# 03_MCU.net
KiCad netlist of a schematic drawn in Altium Designer
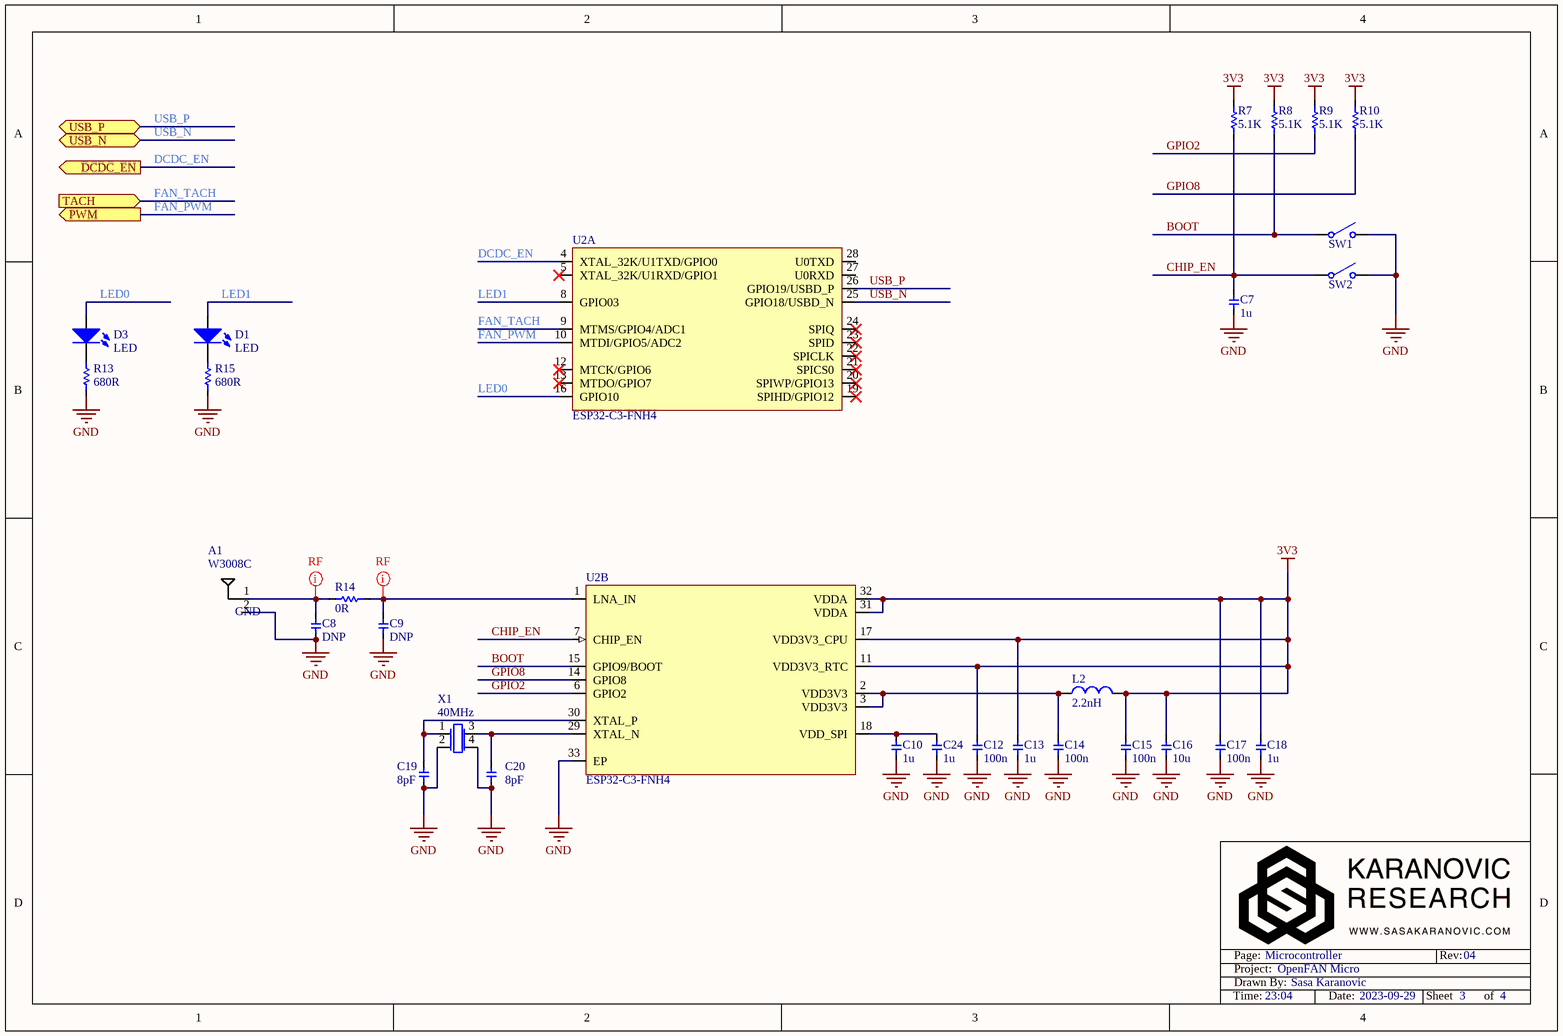
[diagram p0: 03_MCU.SchDoc]

(export (version "E")
  (design (tool "Eeschema 10.0.6"))
  (components
    (comp (ref "A1")
      (value "W3008C")
      (footprint "Footprint_Misc:W3008C")
      (description "2.4GHz Bluetooth, WLAN, Zigbee™ Chip RF Antenna 2.4GHz ~ 2.483GHz 1.3dBi Solder Surface Mount")
      (fields
        (field (name "MANUFACTURER") "Pulse Electronics")
        (field (name "DISTRIBUTOR PART NUMBER") "C581403")
      )
      (libsource (lib "LCSC") (part "ANT-W3008C"))
    )
    (comp (ref "C7")
      (value "1u")
      (footprint "Footprint_Misc:0402")
      (description "Capacitor")
      (fields
        (field (name "MANUFACTURER") "Samsung Electro-Mechanics")
        (field (name "MANUFACTURER PART NUMBER") "CL05A105KO5NNNC")
      )
      (libsource (lib "Schematic_Misc") (part "Cap"))
    )
    (comp (ref "C8")
      (value "DNP")
      (footprint "Footprint_Misc:0402")
      (description "Capacitor")
      (fields (field (name "Comment") "Cap"))
      (libsource (lib "Schematic_Misc") (part "Cap"))
    )
    (comp (ref "C9")
      (value "DNP")
      (footprint "Footprint_Misc:0402")
      (description "Capacitor")
      (fields (field (name "Comment") "Cap"))
      (libsource (lib "Schematic_Misc") (part "Cap"))
    )
    (comp (ref "C10")
      (value "1u")
      (footprint "Footprint_Misc:0402")
      (description "Capacitor")
      (fields
        (field (name "MANUFACTURER") "Samsung Electro-Mechanics")
        (field (name "MANUFACTURER PART NUMBER") "CL05A105KO5NNNC")
      )
      (libsource (lib "Schematic_Misc") (part "Cap"))
    )
    (comp (ref "C12")
      (value "100n")
      (footprint "Footprint_Misc:0402")
      (description "Capacitor")
      (fields
        (field (name "MANUFACTURER") "Samsung Electro-Mechanics")
        (field (name "MANUFACTURER PART NUMBER") "CL05B104KA5NNNC")
      )
      (libsource (lib "Schematic_Misc") (part "Cap"))
    )
    (comp (ref "C13")
      (value "1u")
      (footprint "Footprint_Misc:0402")
      (description "Capacitor")
      (fields
        (field (name "MANUFACTURER") "Samsung Electro-Mechanics")
        (field (name "MANUFACTURER PART NUMBER") "CL05A105KO5NNNC")
      )
      (libsource (lib "Schematic_Misc") (part "Cap"))
    )
    (comp (ref "C14")
      (value "100n")
      (footprint "Footprint_Misc:0402")
      (description "Capacitor")
      (fields
        (field (name "MANUFACTURER") "Samsung Electro-Mechanics")
        (field (name "MANUFACTURER PART NUMBER") "CL05B104KA5NNNC")
      )
      (libsource (lib "Schematic_Misc") (part "Cap"))
    )
    (comp (ref "C15")
      (value "100n")
      (footprint "Footprint_Misc:0402")
      (description "Capacitor")
      (fields
        (field (name "MANUFACTURER") "Samsung Electro-Mechanics")
        (field (name "MANUFACTURER PART NUMBER") "CL05B104KA5NNNC")
      )
      (libsource (lib "Schematic_Misc") (part "Cap"))
    )
    (comp (ref "C16")
      (value "10u")
      (footprint "Footprint_Misc:0402")
      (description "Capacitor")
      (fields
        (field (name "MANUFACTURER") "Murata Electronics")
        (field (name "MANUFACTURER PART NUMBER") "GRM155R61A106ME11D")
      )
      (libsource (lib "Schematic_Misc") (part "Cap"))
    )
    (comp (ref "C17")
      (value "100n")
      (footprint "Footprint_Misc:0402")
      (description "Capacitor")
      (fields
        (field (name "MANUFACTURER") "Samsung Electro-Mechanics")
        (field (name "MANUFACTURER PART NUMBER") "CL05B104KA5NNNC")
      )
      (libsource (lib "Schematic_Misc") (part "Cap"))
    )
    (comp (ref "C18")
      (value "1u")
      (footprint "Footprint_Misc:0402")
      (description "Capacitor")
      (fields
        (field (name "MANUFACTURER") "Samsung Electro-Mechanics")
        (field (name "MANUFACTURER PART NUMBER") "CL05A105KO5NNNC")
      )
      (libsource (lib "Schematic_Misc") (part "Cap"))
    )
    (comp (ref "C19")
      (value "8pF")
      (footprint "Footprint_Misc:0402")
      (description "Capacitor")
      (fields
        (field (name "MANUFACTURER") "Samsung Electro-Mechanics")
        (field (name "MANUFACTURER PART NUMBER") "CL05C080DB51PNC")
      )
      (libsource (lib "Schematic_Misc") (part "Cap"))
    )
    (comp (ref "C20")
      (value "8pF")
      (footprint "Footprint_Misc:0402")
      (description "Capacitor")
      (fields
        (field (name "MANUFACTURER") "Samsung Electro-Mechanics")
        (field (name "MANUFACTURER PART NUMBER") "CL05C080DB51PNC")
      )
      (libsource (lib "Schematic_Misc") (part "Cap"))
    )
    (comp (ref "C24")
      (value "1u")
      (footprint "Footprint_Misc:0402")
      (description "Capacitor")
      (fields
        (field (name "MANUFACTURER") "Samsung Electro-Mechanics")
        (field (name "MANUFACTURER PART NUMBER") "CL05A105KO5NNNC")
      )
      (libsource (lib "Schematic_Misc") (part "Cap"))
    )
    (comp (ref "D1")
      (value "LED")
      (footprint "CD1608-0603")
      (description "Typical RED GaAs LED")
      (fields
        (field (name "DISTRIBUTOR PART NUMBER") "C2900098")
        (field (name "MANUFACTURER") "ams-OSRAM USA INC.")
      )
      (libsource (lib "Schematic_Misc") (part "LED"))
    )
    (comp (ref "D3")
      (value "LED")
      (footprint "CD1608-0603")
      (description "Typical RED GaAs LED")
      (fields
        (field (name "DISTRIBUTOR PART NUMBER") "C2900098")
        (field (name "MANUFACTURER") "ams-OSRAM USA INC.")
      )
      (libsource (lib "Schematic_Misc") (part "LED"))
    )
    (comp (ref "L2")
      (value "2.2nH")
      (footprint "Footprint_Misc:0402")
      (description "1.1A 2.2nH 100mΩ 0603 Inductors (SMD) ROHS")
      (fields
        (field (name "MANUFACTURER") "Murata Electronics")
        (field (name "MANUFACTURER PART NUMBER") "LQG15HS2N2B02D")
      )
      (libsource (lib "LCSC") (part "Inductor - 2.2nH"))
    )
    (comp (ref "R7")
      (value "5.1K")
      (footprint "Footprint_Misc:0402")
      (description "Resistor")
      (fields (field (name "DISTRIBUTOR PART NUMBER") "C105872") (field (name "MANUFACTURER") "YAGEO"))
      (libsource (lib "Schematic_Misc") (part "Res"))
    )
    (comp (ref "R8")
      (value "5.1K")
      (footprint "Footprint_Misc:0402")
      (description "Resistor")
      (fields (field (name "DISTRIBUTOR PART NUMBER") "C105872") (field (name "MANUFACTURER") "YAGEO"))
      (libsource (lib "Schematic_Misc") (part "Res"))
    )
    (comp (ref "R9")
      (value "5.1K")
      (footprint "Footprint_Misc:0402")
      (description "Resistor")
      (fields (field (name "DISTRIBUTOR PART NUMBER") "C105872") (field (name "MANUFACTURER") "YAGEO"))
      (libsource (lib "Schematic_Misc") (part "Res"))
    )
    (comp (ref "R10")
      (value "5.1K")
      (footprint "Footprint_Misc:0402")
      (description "Resistor")
      (fields (field (name "DISTRIBUTOR PART NUMBER") "C105872") (field (name "MANUFACTURER") "YAGEO"))
      (libsource (lib "Schematic_Misc") (part "Res"))
    )
    (comp (ref "R13")
      (value "680R")
      (footprint "Footprint_Misc:0402")
      (description "Resistor")
      (fields (field (name "DISTRIBUTOR PART NUMBER") "C6378047") (field (name "MANUFACTURER") "YAGEO"))
      (libsource (lib "Schematic_Misc") (part "Res"))
    )
    (comp (ref "R14")
      (value "0R")
      (footprint "Footprint_Misc:0402")
      (description "Resistor")
      (fields (field (name "DISTRIBUTOR PART NUMBER") "C60485") (field (name "MANUFACTURER") "YAGEO"))
      (libsource (lib "Schematic_Misc") (part "Res"))
    )
    (comp (ref "R15")
      (value "680R")
      (footprint "Footprint_Misc:0402")
      (description "Resistor")
      (fields (field (name "DISTRIBUTOR PART NUMBER") "C6378047") (field (name "MANUFACTURER") "YAGEO"))
      (libsource (lib "Schematic_Misc") (part "Res"))
    )
    (comp (ref "SW1")
      (value "Switch")
      (footprint "Footprint_Misc:Switch-XDTD-0304-215")
      (description "50mA Surface Mount SPST 100MΩ 100,000 Times 12V 160gf@±50gf SMD Tactile Switches ROHS")
      (fields
        (field (name "MANUFACTURER") "Lian Xin Technology")
        (field (name "MANUFACTURER PART NUMBER") "XDTD-0304-215")
      )
      (libsource (lib "Schematic_Misc") (part "Switch -XDTD-0304-215"))
    )
    (comp (ref "SW2")
      (value "Switch")
      (footprint "Footprint_Misc:Switch-XDTD-0304-215")
      (description "50mA Surface Mount SPST 100MΩ 100,000 Times 12V 160gf@±50gf SMD Tactile Switches ROHS")
      (fields
        (field (name "MANUFACTURER") "Lian Xin Technology")
        (field (name "MANUFACTURER PART NUMBER") "XDTD-0304-215")
      )
      (libsource (lib "Schematic_Misc") (part "Switch -XDTD-0304-215"))
    )
    (comp (ref "U2")
      (value "ESP32-C3-FNH4")
      (footprint "Footprint_Misc:QFN50P500X500X100_HS-33N")
      (description "Ultra-Low-Power SoC with RISC-V Single-Core CPU 2.4 GHz Wi-Fi (802.11 b/g/n) and Bluetooth® 5 (LE)")
      (fields
        (field (name "MANUFACTURER") "Espressif Systems")
        (field (name "DISTRIBUTOR PART NUMBER") "C2858491")
      )
      (libsource (lib "Schematic_Misc") (part "ESP32-C3-FNH4"))
    )
    (comp (ref "X1")
      (value "40MHz")
      (footprint "Footprint_Misc:XTAL-4LEAD-2016")
      (description "40MHz 9pF ±10ppm SMD2016-4P Crystals ROHS")
      (fields (field (name "MANUFACTURER") "TROQ") (field (name "MANUFACTURER PART NUMBER") "R940000171"))
      (libsource (lib "Schematic_Misc") (part "XTAL-40MHz-R940000171"))
    )
  )
  (nets
    (net (code "1") (name "/BOOT") (class "Default")
      (node (ref "R8") (pin "2") (pinfunction "2_2") (pintype "passive"))
      (node (ref "SW1") (pin "1") (pinfunction "COMMON1_1") (pintype "passive"))
      (node (ref "U2") (pin "15") (pinfunction "GPIO9/BOOT_15") (pintype "passive"))
    )
    (net (code "2") (name "/CHIP_EN") (class "Default")
      (node (ref "C7") (pin "2") (pinfunction "2_2") (pintype "passive"))
      (node (ref "R7") (pin "2") (pinfunction "2_2") (pintype "passive"))
      (node (ref "SW2") (pin "1") (pinfunction "COMMON1_1") (pintype "passive"))
      (node (ref "U2") (pin "7") (pinfunction "CHIP_EN_7") (pintype "input"))
    )
    (net (code "3") (name "/DCDC_EN") (class "Default")
      (node (ref "U2") (pin "4") (pinfunction "XTAL_32K/U1TXD/GPIO0_4") (pintype "passive"))
    )
    (net (code "4") (name "/FAN_PWM") (class "Default")
      (node (ref "U2") (pin "10") (pinfunction "MTDI/GPIO5/ADC2_10") (pintype "passive"))
    )
    (net (code "5") (name "/FAN_TACH") (class "Default")
      (node (ref "U2") (pin "9") (pinfunction "MTMS/GPIO4/ADC1_9") (pintype "passive"))
    )
    (net (code "6") (name "/GPIO2") (class "Default")
      (node (ref "R9") (pin "2") (pinfunction "2_2") (pintype "passive"))
      (node (ref "U2") (pin "6") (pinfunction "GPIO2_6") (pintype "passive"))
    )
    (net (code "7") (name "/GPIO8") (class "Default")
      (node (ref "R10") (pin "2") (pinfunction "2_2") (pintype "passive"))
      (node (ref "U2") (pin "14") (pinfunction "GPIO8_14") (pintype "passive"))
    )
    (net (code "8") (name "/LED0") (class "Default")
      (node (ref "D3") (pin "A") (pinfunction "A_A") (pintype "passive"))
      (node (ref "U2") (pin "16") (pinfunction "GPIO10_16") (pintype "passive"))
    )
    (net (code "9") (name "/LED1") (class "Default")
      (node (ref "D1") (pin "A") (pinfunction "A_A") (pintype "passive"))
      (node (ref "U2") (pin "8") (pinfunction "GPIO03_8") (pintype "passive"))
    )
    (net (code "10") (name "/USB_N") (class "Default")
      (node (ref "U2") (pin "25") (pinfunction "GPIO18/USBD_N_25") (pintype "passive"))
    )
    (net (code "11") (name "/USB_P") (class "Default")
      (node (ref "U2") (pin "26") (pinfunction "GPIO19/USBD_P_26") (pintype "passive"))
    )
    (net (code "12") (name "3V3") (class "Default")
      (node (ref "C12") (pin "2") (pinfunction "2_2") (pintype "passive"))
      (node (ref "C13") (pin "2") (pinfunction "2_2") (pintype "passive"))
      (node (ref "C15") (pin "2") (pinfunction "2_2") (pintype "passive"))
      (node (ref "C16") (pin "2") (pinfunction "2_2") (pintype "passive"))
      (node (ref "C17") (pin "2") (pinfunction "2_2") (pintype "passive"))
      (node (ref "C18") (pin "2") (pinfunction "2_2") (pintype "passive"))
      (node (ref "L2") (pin "2") (pinfunction "2_2") (pintype "passive"))
      (node (ref "R10") (pin "1") (pinfunction "1_1") (pintype "passive"))
      (node (ref "R7") (pin "1") (pinfunction "1_1") (pintype "passive"))
      (node (ref "R8") (pin "1") (pinfunction "1_1") (pintype "passive"))
      (node (ref "R9") (pin "1") (pinfunction "1_1") (pintype "passive"))
      (node (ref "U2") (pin "11") (pinfunction "VDD3V3_RTC_11") (pintype "passive"))
      (node (ref "U2") (pin "17") (pinfunction "VDD3V3_CPU_17") (pintype "passive"))
      (node (ref "U2") (pin "31") (pinfunction "VDDA_31") (pintype "passive"))
      (node (ref "U2") (pin "32") (pinfunction "VDDA_32") (pintype "passive"))
    )
    (net (code "13") (name "GND") (class "Default")
      (node (ref "A1") (pin "2") (pinfunction "2_2") (pintype "passive"))
      (node (ref "C10") (pin "1") (pinfunction "1_1") (pintype "passive"))
      (node (ref "C12") (pin "1") (pinfunction "1_1") (pintype "passive"))
      (node (ref "C13") (pin "1") (pinfunction "1_1") (pintype "passive"))
      (node (ref "C14") (pin "1") (pinfunction "1_1") (pintype "passive"))
      (node (ref "C15") (pin "1") (pinfunction "1_1") (pintype "passive"))
      (node (ref "C16") (pin "1") (pinfunction "1_1") (pintype "passive"))
      (node (ref "C17") (pin "1") (pinfunction "1_1") (pintype "passive"))
      (node (ref "C18") (pin "1") (pinfunction "1_1") (pintype "passive"))
      (node (ref "C19") (pin "2") (pinfunction "2_2") (pintype "passive"))
      (node (ref "C20") (pin "1") (pinfunction "1_1") (pintype "passive"))
      (node (ref "C24") (pin "1") (pinfunction "1_1") (pintype "passive"))
      (node (ref "C7") (pin "1") (pinfunction "1_1") (pintype "passive"))
      (node (ref "C8") (pin "1") (pinfunction "1_1") (pintype "passive"))
      (node (ref "C9") (pin "1") (pinfunction "1_1") (pintype "passive"))
      (node (ref "R13") (pin "1") (pinfunction "1_1") (pintype "passive"))
      (node (ref "R15") (pin "1") (pinfunction "1_1") (pintype "passive"))
      (node (ref "SW1") (pin "2") (pinfunction "COMMON2_2") (pintype "passive"))
      (node (ref "SW2") (pin "2") (pinfunction "COMMON2_2") (pintype "passive"))
      (node (ref "U2") (pin "33") (pinfunction "EP_33") (pintype "passive"))
      (node (ref "X1") (pin "2") (pinfunction "GND_2") (pintype "passive"))
      (node (ref "X1") (pin "4") (pinfunction "GND_4") (pintype "passive"))
    )
    (net (code "14") (name "Net-(A1-Pad1)") (class "Default")
      (node (ref "A1") (pin "1") (pinfunction "1_1") (pintype "passive"))
      (node (ref "C8") (pin "2") (pinfunction "2_2") (pintype "passive"))
      (node (ref "R14") (pin "1") (pinfunction "1_1") (pintype "passive"))
    )
    (net (code "15") (name "Net-(C14-Pad2)") (class "Default")
      (node (ref "C14") (pin "2") (pinfunction "2_2") (pintype "passive"))
      (node (ref "L2") (pin "1") (pinfunction "1_1") (pintype "passive"))
      (node (ref "U2") (pin "2") (pinfunction "VDD3V3_2") (pintype "passive"))
      (node (ref "U2") (pin "3") (pinfunction "VDD3V3_3") (pintype "passive"))
    )
    (net (code "16") (name "Net-(D1-PadK)") (class "Default")
      (node (ref "D1") (pin "K") (pinfunction "K_K") (pintype "passive"))
      (node (ref "R15") (pin "2") (pinfunction "2_2") (pintype "passive"))
    )
    (net (code "17") (name "Net-(D3-PadK)") (class "Default")
      (node (ref "D3") (pin "K") (pinfunction "K_K") (pintype "passive"))
      (node (ref "R13") (pin "2") (pinfunction "2_2") (pintype "passive"))
    )
    (net (code "18") (name "Net-(U2B-LNA_IN)") (class "Default")
      (node (ref "C9") (pin "2") (pinfunction "2_2") (pintype "passive"))
      (node (ref "R14") (pin "2") (pinfunction "2_2") (pintype "passive"))
      (node (ref "U2") (pin "1") (pinfunction "LNA_IN_1") (pintype "passive"))
    )
    (net (code "19") (name "Net-(U2B-VDD_SPI)") (class "Default")
      (node (ref "C10") (pin "2") (pinfunction "2_2") (pintype "passive"))
      (node (ref "C24") (pin "2") (pinfunction "2_2") (pintype "passive"))
      (node (ref "U2") (pin "18") (pinfunction "VDD_SPI_18") (pintype "passive"))
    )
    (net (code "20") (name "Net-(U2B-XTAL_N)") (class "Default")
      (node (ref "C20") (pin "2") (pinfunction "2_2") (pintype "passive"))
      (node (ref "U2") (pin "29") (pinfunction "XTAL_N_29") (pintype "passive"))
      (node (ref "X1") (pin "3") (pinfunction "OSC3_3") (pintype "passive"))
    )
    (net (code "21") (name "Net-(U2B-XTAL_P)") (class "Default")
      (node (ref "C19") (pin "1") (pinfunction "1_1") (pintype "passive"))
      (node (ref "U2") (pin "30") (pinfunction "XTAL_P_30") (pintype "passive"))
      (node (ref "X1") (pin "1") (pinfunction "OSC1_1") (pintype "passive"))
    )
    (net (code "22") (name "unconnected-(U2A-MTCK{slash}GPIO6-Pad12)") (class "Default")
      (node (ref "U2") (pin "12") (pinfunction "MTCK/GPIO6_12") (pintype "passive+no_connect"))
    )
    (net (code "23") (name "unconnected-(U2A-MTDO{slash}GPIO7-Pad13)") (class "Default")
      (node (ref "U2") (pin "13") (pinfunction "MTDO/GPIO7_13") (pintype "passive+no_connect"))
    )
    (net (code "24") (name "unconnected-(U2A-SPICLK-Pad22)") (class "Default")
      (node (ref "U2") (pin "22") (pinfunction "SPICLK_22") (pintype "passive+no_connect"))
    )
    (net (code "25") (name "unconnected-(U2A-SPICS0-Pad21)") (class "Default")
      (node (ref "U2") (pin "21") (pinfunction "SPICS0_21") (pintype "passive+no_connect"))
    )
    (net (code "26") (name "unconnected-(U2A-SPID-Pad23)") (class "Default")
      (node (ref "U2") (pin "23") (pinfunction "SPID_23") (pintype "passive+no_connect"))
    )
    (net (code "27") (name "unconnected-(U2A-SPIHD{slash}GPIO12-Pad19)") (class "Default")
      (node (ref "U2") (pin "19") (pinfunction "SPIHD/GPIO12_19") (pintype "passive+no_connect"))
    )
    (net (code "28") (name "unconnected-(U2A-SPIQ-Pad24)") (class "Default")
      (node (ref "U2") (pin "24") (pinfunction "SPIQ_24") (pintype "passive+no_connect"))
    )
    (net (code "29") (name "unconnected-(U2A-SPIWP{slash}GPIO13-Pad20)") (class "Default")
      (node (ref "U2") (pin "20") (pinfunction "SPIWP/GPIO13_20") (pintype "passive+no_connect"))
    )
    (net (code "30") (name "unconnected-(U2A-U0RXD-Pad27)") (class "Default")
      (node (ref "U2") (pin "27") (pinfunction "U0RXD_27") (pintype "passive"))
    )
    (net (code "31") (name "unconnected-(U2A-U0TXD-Pad28)") (class "Default")
      (node (ref "U2") (pin "28") (pinfunction "U0TXD_28") (pintype "passive"))
    )
    (net (code "32") (name "unconnected-(U2A-XTAL_32K{slash}U1RXD{slash}GPIO1-Pad5)") (class "Default")
      (node (ref "U2") (pin "5") (pinfunction "XTAL_32K/U1RXD/GPIO1_5") (pintype "passive+no_connect"))
    )
  )
)
